# Sincronismo.net
KiCad netlist of a schematic drawn in Altium Designer
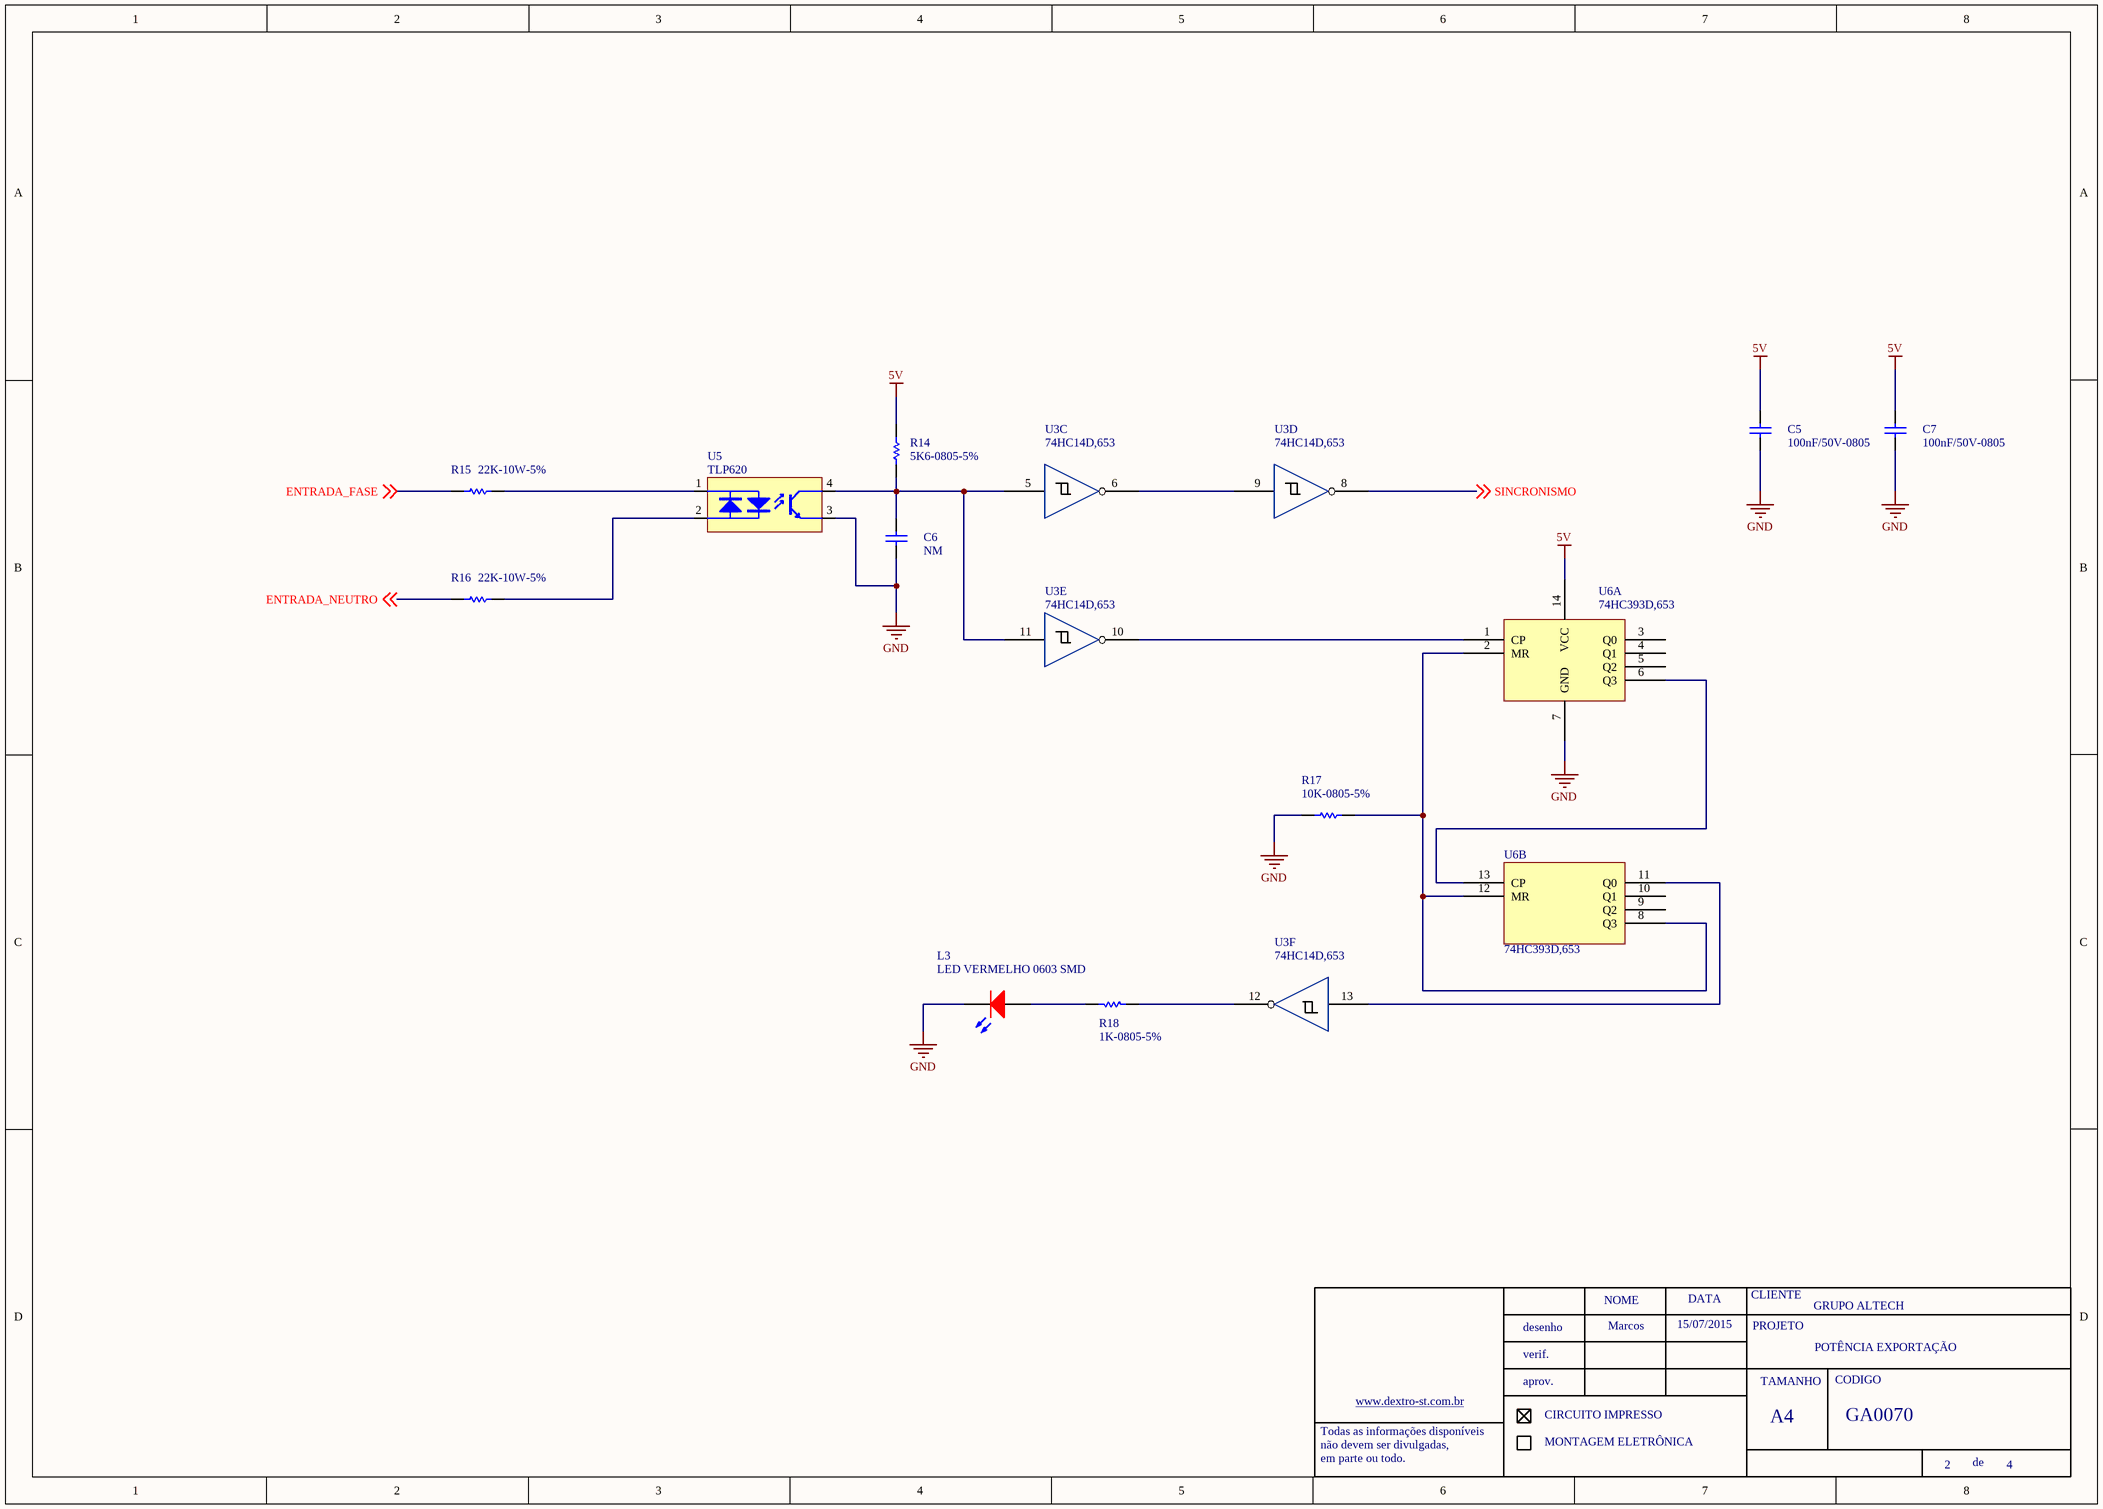
[diagram p0: Sincronismo.SchDoc]

(export (version "E")
  (design (tool "Eeschema 10.0.6"))
  (components
    (comp (ref "C5")
      (value "100nF/50V-0805")
      (footprint "0805-REVISADO ONDA")
      (libsource (lib "AquinoLib") (part "100nF/50-0805-NPO"))
    )
    (comp (ref "C6")
      (value "NM")
      (footprint "0805-REVISADO ONDA")
      (description "100nF/50-0805-NPO")
      (libsource (lib "AquinoLib") (part "100nF/50-0805-NPO"))
    )
    (comp (ref "C7")
      (value "100nF/50V-0805")
      (footprint "0805-REVISADO ONDA")
      (libsource (lib "AquinoLib") (part "100nF/50-0805-NPO"))
    )
    (comp (ref "L3")
      (value "LED VERMELHO 0603 SMD")
      (footprint "LED 1206")
      (libsource (lib "AquinoLib") (part "LED VERMELHO 0603 SMD"))
    )
    (comp (ref "R14")
      (value "5K6-0805-5%")
      (footprint "0805-REVISADO ONDA")
      (description "22K-0805-5%")
      (libsource (lib "AquinoLib") (part "22K-0805-5%"))
    )
    (comp (ref "R15")
      (value "22K-10W-5%")
      (footprint "RESISTOR 10W CERAMICO")
      (description "22K-0805-5%")
      (libsource (lib "AquinoLib") (part "22K-0805-5%"))
    )
    (comp (ref "R16")
      (value "22K-10W-5%")
      (footprint "RESISTOR 10W CERAMICO")
      (description "22K-0805-5%")
      (libsource (lib "AquinoLib") (part "22K-0805-5%"))
    )
    (comp (ref "R17")
      (value "10K-0805-5%")
      (footprint "0805-REVISADO ONDA")
      (libsource (lib "AquinoLib") (part "10K-0805-5%"))
    )
    (comp (ref "R18")
      (value "1K-0805-5%")
      (footprint "0805-REVISADO ONDA")
      (libsource (lib "AquinoLib") (part "1K-0805-5%"))
    )
    (comp (ref "U3")
      (value "74HC14D,653")
      (footprint "SOIC 14 PINOS")
      (description "74HC14D")
      (libsource (lib "AquinoLib") (part "74HC14D"))
    )
    (comp (ref "U5")
      (value "TLP620")
      (footprint "DIP-4")
      (description "PC814")
      (libsource (lib "AquinoLib") (part "PC814"))
    )
    (comp (ref "U6")
      (value "74HC393D,653")
      (footprint "SOIC 14 PINOS")
      (libsource (lib "AquinoLib") (part "74HC393"))
    )
  )
  (nets
    (net (code "1") (name "5V") (class "Default")
      (node (ref "C5") (pin "2") (pinfunction "2_2") (pintype "passive"))
      (node (ref "C7") (pin "2") (pinfunction "2_2") (pintype "passive"))
      (node (ref "R14") (pin "2") (pinfunction "2_2") (pintype "passive"))
      (node (ref "U6") (pin "14") (pinfunction "VCC_14") (pintype "passive"))
    )
    (net (code "2") (name "ENTRADA_FASE") (class "Default")
      (node (ref "R15") (pin "1") (pinfunction "1_1") (pintype "passive"))
    )
    (net (code "3") (name "ENTRADA_NEUTRO") (class "Default")
      (node (ref "R16") (pin "1") (pinfunction "1_1") (pintype "passive"))
    )
    (net (code "4") (name "GND") (class "Default")
      (node (ref "C5") (pin "1") (pinfunction "1_1") (pintype "passive"))
      (node (ref "C6") (pin "1") (pinfunction "1_1") (pintype "passive"))
      (node (ref "C7") (pin "1") (pinfunction "1_1") (pintype "passive"))
      (node (ref "L3") (pin "2") (pinfunction "K_2") (pintype "passive"))
      (node (ref "R17") (pin "1") (pinfunction "1_1") (pintype "passive"))
      (node (ref "U5") (pin "3") (pinfunction "E_3") (pintype "passive"))
      (node (ref "U6") (pin "7") (pinfunction "GND_7") (pintype "passive"))
    )
    (net (code "5") (name "Net-(L3-A)") (class "Default")
      (node (ref "L3") (pin "1") (pinfunction "A_1") (pintype "passive"))
      (node (ref "R18") (pin "2") (pinfunction "2_2") (pintype "passive"))
    )
    (net (code "6") (name "Net-(R18-Pad1)") (class "Default")
      (node (ref "R18") (pin "1") (pinfunction "1_1") (pintype "passive"))
      (node (ref "U3") (pin "12") (pinfunction "12_12") (pintype "passive"))
    )
    (net (code "7") (name "Net-(U3-Pad6)") (class "Default")
      (node (ref "U3") (pin "6") (pinfunction "6_6") (pintype "passive"))
      (node (ref "U3") (pin "9") (pinfunction "9_9") (pintype "passive"))
    )
    (net (code "8") (name "Net-(U5-A)") (class "Default")
      (node (ref "R15") (pin "2") (pinfunction "2_2") (pintype "passive"))
      (node (ref "U5") (pin "1") (pinfunction "A_1") (pintype "passive"))
    )
    (net (code "9") (name "Net-(U5-C)") (class "Default")
      (node (ref "C6") (pin "2") (pinfunction "2_2") (pintype "passive"))
      (node (ref "R14") (pin "1") (pinfunction "1_1") (pintype "passive"))
      (node (ref "U3") (pin "11") (pinfunction "11_11") (pintype "passive"))
      (node (ref "U3") (pin "5") (pinfunction "5_5") (pintype "passive"))
      (node (ref "U5") (pin "4") (pinfunction "C_4") (pintype "passive"))
    )
    (net (code "10") (name "Net-(U5-K)") (class "Default")
      (node (ref "R16") (pin "2") (pinfunction "2_2") (pintype "passive"))
      (node (ref "U5") (pin "2") (pinfunction "K_2") (pintype "passive"))
    )
    (net (code "11") (name "Net-(U6A-CP)") (class "Default")
      (node (ref "U3") (pin "10") (pinfunction "10_10") (pintype "passive"))
      (node (ref "U6") (pin "1") (pinfunction "CP_1") (pintype "passive"))
    )
    (net (code "12") (name "Net-(U6A-MR)") (class "Default")
      (node (ref "R17") (pin "2") (pinfunction "2_2") (pintype "passive"))
      (node (ref "U6") (pin "12") (pinfunction "MR_12") (pintype "passive"))
      (node (ref "U6") (pin "2") (pinfunction "MR_2") (pintype "passive"))
      (node (ref "U6") (pin "8") (pinfunction "Q3_8") (pintype "passive"))
    )
    (net (code "13") (name "Net-(U6A-Q3)") (class "Default")
      (node (ref "U6") (pin "13") (pinfunction "CP_13") (pintype "passive"))
      (node (ref "U6") (pin "6") (pinfunction "Q3_6") (pintype "passive"))
    )
    (net (code "14") (name "Net-(U6B-Q0)") (class "Default")
      (node (ref "U3") (pin "13") (pinfunction "13_13") (pintype "passive"))
      (node (ref "U6") (pin "11") (pinfunction "Q0_11") (pintype "passive"))
    )
    (net (code "15") (name "SINCRONISMO") (class "Default")
      (node (ref "U3") (pin "8") (pinfunction "8_8") (pintype "passive"))
    )
    (net (code "16") (name "unconnected-(U6A-Q0-Pad3)") (class "Default")
      (node (ref "U6") (pin "3") (pinfunction "Q0_3") (pintype "passive"))
    )
    (net (code "17") (name "unconnected-(U6A-Q1-Pad4)") (class "Default")
      (node (ref "U6") (pin "4") (pinfunction "Q1_4") (pintype "passive"))
    )
    (net (code "18") (name "unconnected-(U6A-Q2-Pad5)") (class "Default")
      (node (ref "U6") (pin "5") (pinfunction "Q2_5") (pintype "passive"))
    )
    (net (code "19") (name "unconnected-(U6B-Q1-Pad10)") (class "Default")
      (node (ref "U6") (pin "10") (pinfunction "Q1_10") (pintype "passive"))
    )
    (net (code "20") (name "unconnected-(U6B-Q2-Pad9)") (class "Default")
      (node (ref "U6") (pin "9") (pinfunction "Q2_9") (pintype "passive"))
    )
  )
)
